# shield_confortimetro_bia.net
KiCad netlist of a schematic drawn in EAGLE
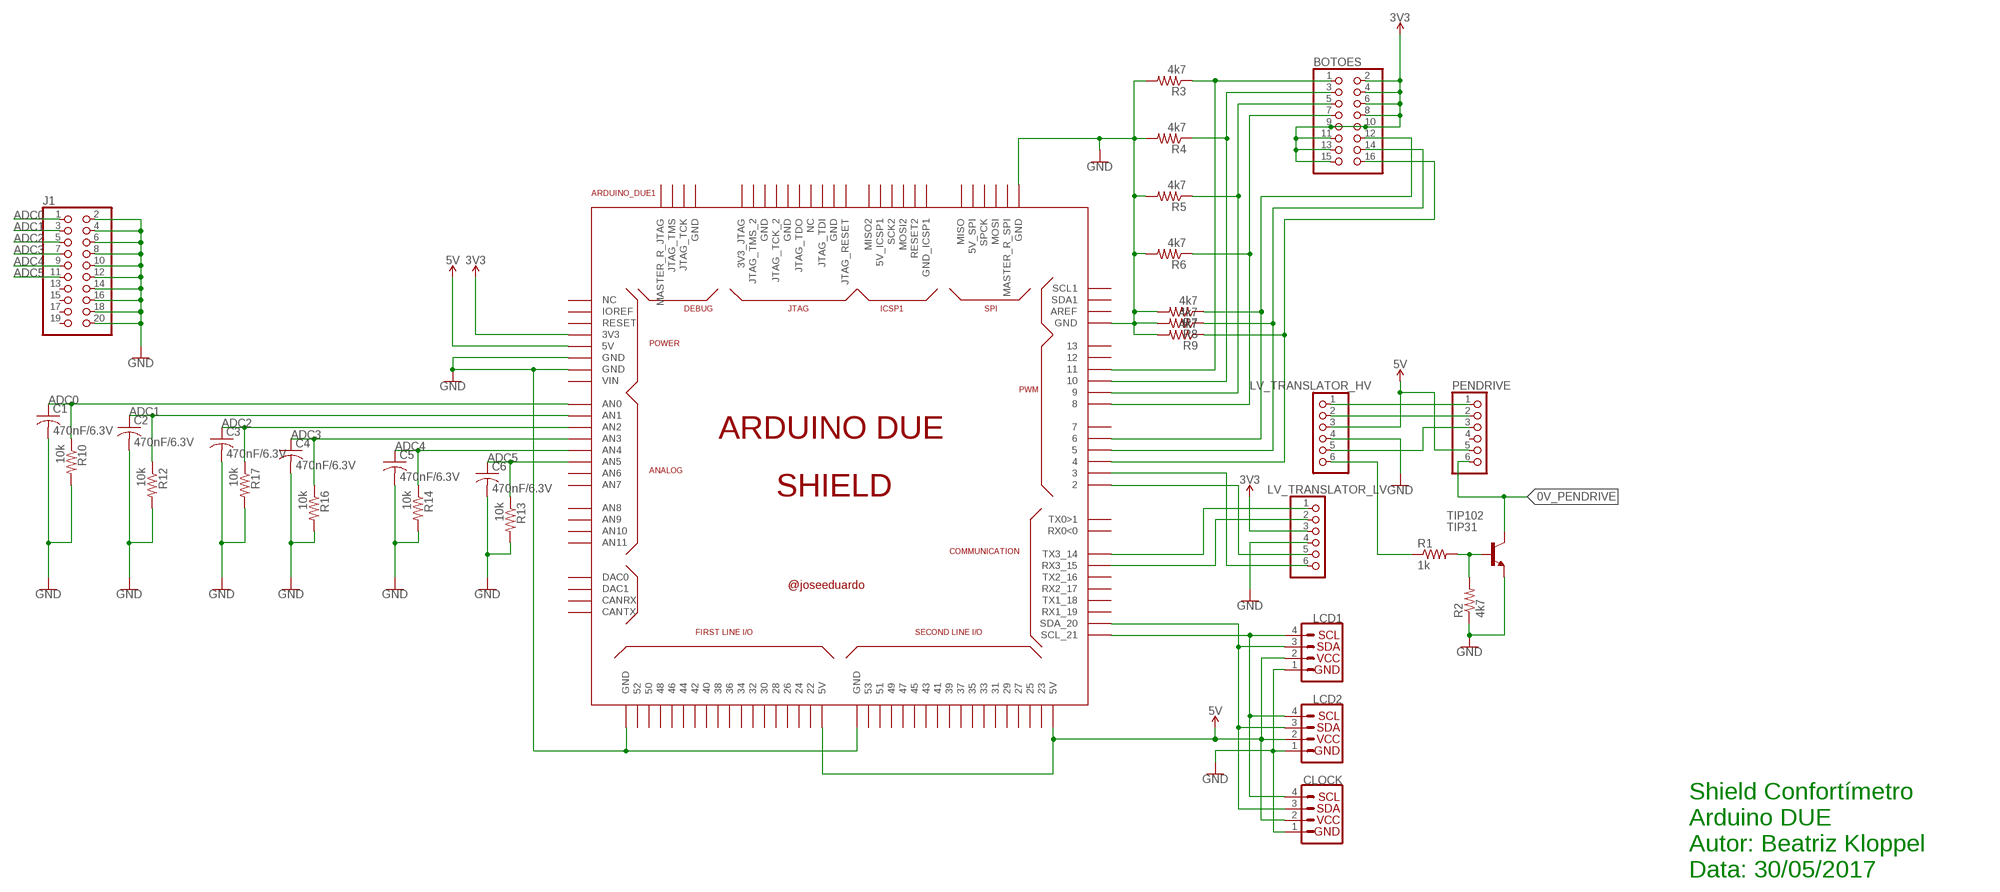
[diagram p0: schematic, sheet 1]

(export (version "E")
  (design (tool "Eeschema 10.0.6"))
  (components
    (comp (ref "ARDUINO_DUE1")
      (value "ARDUINO_DUE_SHIELD")
      (footprint "eagle-import:ARDUINO_DUE_SHIELD")
      (libsource (lib "eagle-import") (part "ARDUINO_DUE_SHIELD"))
    )
    (comp (ref "BOTOES")
      (value "PINHD-2X8")
      (footprint "eagle-import:2X08")
      (libsource (lib "eagle-import") (part "PINHD-2X8"))
    )
    (comp (ref "C1")
      (value "470nF/6.3V")
      (footprint "eagle-import:C050-030X075")
      (libsource (lib "eagle-import") (part "C-US050-030X075"))
    )
    (comp (ref "C2")
      (value "470nF/6.3V")
      (footprint "eagle-import:C050-030X075")
      (libsource (lib "eagle-import") (part "C-US050-030X075"))
    )
    (comp (ref "C3")
      (value "470nF/6.3V")
      (footprint "eagle-import:C050-030X075")
      (libsource (lib "eagle-import") (part "C-US050-030X075"))
    )
    (comp (ref "C4")
      (value "470nF/6.3V")
      (footprint "eagle-import:C050-030X075")
      (libsource (lib "eagle-import") (part "C-US050-030X075"))
    )
    (comp (ref "C5")
      (value "470nF/6.3V")
      (footprint "eagle-import:C050-030X075")
      (libsource (lib "eagle-import") (part "C-US050-030X075"))
    )
    (comp (ref "C6")
      (value "470nF/6.3V")
      (footprint "eagle-import:C050-030X075")
      (libsource (lib "eagle-import") (part "C-US050-030X075"))
    )
    (comp (ref "CLOCK")
      (value "I2C_STANDARD")
      (footprint "eagle-import:1X04")
      (libsource (lib "eagle-import") (part "I2C_STANDARD"))
    )
    (comp (ref "J1")
      (value "PINHD-2X10")
      (footprint "eagle-import:2X10")
      (libsource (lib "eagle-import") (part "PINHD-2X10"))
    )
    (comp (ref "LCD1")
      (value "I2C_STANDARD")
      (footprint "eagle-import:1X04")
      (libsource (lib "eagle-import") (part "I2C_STANDARD"))
    )
    (comp (ref "LCD2")
      (value "I2C_STANDARD")
      (footprint "eagle-import:1X04")
      (libsource (lib "eagle-import") (part "I2C_STANDARD"))
    )
    (comp (ref "LV_TRANSLATOR_HV")
      (value "PINHD-1X6")
      (footprint "eagle-import:1X06")
      (libsource (lib "eagle-import") (part "PINHD-1X6"))
    )
    (comp (ref "LV_TRANSLATOR_LV")
      (value "PINHD-1X6")
      (footprint "eagle-import:1X06")
      (libsource (lib "eagle-import") (part "PINHD-1X6"))
    )
    (comp (ref "PENDRIVE")
      (value "PINHD-1X6")
      (footprint "eagle-import:1X06")
      (libsource (lib "eagle-import") (part "PINHD-1X6"))
    )
    (comp (ref "R1")
      (value "1k")
      (footprint "eagle-import:0309_12")
      (libsource (lib "eagle-import") (part "R-US_0309/12"))
    )
    (comp (ref "R2")
      (value "4k7")
      (footprint "eagle-import:0309_12")
      (libsource (lib "eagle-import") (part "R-US_0309/12"))
    )
    (comp (ref "R3")
      (value "4k7")
      (footprint "eagle-import:0309_12")
      (libsource (lib "eagle-import") (part "R-US_0309/12"))
    )
    (comp (ref "R4")
      (value "4k7")
      (footprint "eagle-import:0309_12")
      (libsource (lib "eagle-import") (part "R-US_0309/12"))
    )
    (comp (ref "R5")
      (value "4k7")
      (footprint "eagle-import:0309_12")
      (libsource (lib "eagle-import") (part "R-US_0309/12"))
    )
    (comp (ref "R6")
      (value "4k7")
      (footprint "eagle-import:0309_12")
      (libsource (lib "eagle-import") (part "R-US_0309/12"))
    )
    (comp (ref "R7")
      (value "4k7")
      (footprint "eagle-import:0309_12")
      (libsource (lib "eagle-import") (part "R-US_0309/12"))
    )
    (comp (ref "R8")
      (value "4k7")
      (footprint "eagle-import:0309_12")
      (libsource (lib "eagle-import") (part "R-US_0309/12"))
    )
    (comp (ref "R9")
      (value "4k7")
      (footprint "eagle-import:0309_12")
      (libsource (lib "eagle-import") (part "R-US_0309/12"))
    )
    (comp (ref "R10")
      (value "10k")
      (footprint "eagle-import:0309_12")
      (libsource (lib "eagle-import") (part "R-US_0309/12"))
    )
    (comp (ref "R12")
      (value "10k")
      (footprint "eagle-import:0309_12")
      (libsource (lib "eagle-import") (part "R-US_0309/12"))
    )
    (comp (ref "R13")
      (value "10k")
      (footprint "eagle-import:0309_12")
      (libsource (lib "eagle-import") (part "R-US_0309/12"))
    )
    (comp (ref "R14")
      (value "10k")
      (footprint "eagle-import:0309_12")
      (libsource (lib "eagle-import") (part "R-US_0309/12"))
    )
    (comp (ref "R16")
      (value "10k")
      (footprint "eagle-import:0309_12")
      (libsource (lib "eagle-import") (part "R-US_0309/12"))
    )
    (comp (ref "R17")
      (value "10k")
      (footprint "eagle-import:0309_12")
      (libsource (lib "eagle-import") (part "R-US_0309/12"))
    )
    (comp (ref "TIP102")
      (value "TIP31")
      (footprint "eagle-import:TO220")
      (libsource (lib "eagle-import") (part "TIP31"))
    )
  )
  (nets
    (net (code "1") (name "/ADC0") (class "Default")
      (node (ref "ARDUINO_DUE1") (pin "A0") (pinfunction "AN0_A0") (pintype "bidirectional"))
      (node (ref "C1") (pin "1") (pinfunction "1_1") (pintype "passive"))
      (node (ref "J1") (pin "1") (pinfunction "1_1") (pintype "passive"))
      (node (ref "R10") (pin "1") (pinfunction "1_1") (pintype "passive"))
    )
    (net (code "2") (name "/ADC1") (class "Default")
      (node (ref "ARDUINO_DUE1") (pin "A1") (pinfunction "AN1_A1") (pintype "bidirectional"))
      (node (ref "C2") (pin "1") (pinfunction "1_1") (pintype "passive"))
      (node (ref "J1") (pin "3") (pinfunction "3_3") (pintype "passive"))
      (node (ref "R12") (pin "1") (pinfunction "1_1") (pintype "passive"))
    )
    (net (code "3") (name "/ADC2") (class "Default")
      (node (ref "ARDUINO_DUE1") (pin "A2") (pinfunction "AN2_A2") (pintype "bidirectional"))
      (node (ref "C3") (pin "1") (pinfunction "1_1") (pintype "passive"))
      (node (ref "J1") (pin "5") (pinfunction "5_5") (pintype "passive"))
      (node (ref "R17") (pin "1") (pinfunction "1_1") (pintype "passive"))
    )
    (net (code "4") (name "/ADC3") (class "Default")
      (node (ref "ARDUINO_DUE1") (pin "A3") (pinfunction "AN3_A3") (pintype "bidirectional"))
      (node (ref "C4") (pin "1") (pinfunction "1_1") (pintype "passive"))
      (node (ref "J1") (pin "7") (pinfunction "7_7") (pintype "passive"))
      (node (ref "R16") (pin "1") (pinfunction "1_1") (pintype "passive"))
    )
    (net (code "5") (name "/ADC4") (class "Default")
      (node (ref "ARDUINO_DUE1") (pin "A4") (pinfunction "AN4_A4") (pintype "bidirectional"))
      (node (ref "C5") (pin "1") (pinfunction "1_1") (pintype "passive"))
      (node (ref "J1") (pin "9") (pinfunction "9_9") (pintype "passive"))
      (node (ref "R14") (pin "1") (pinfunction "1_1") (pintype "passive"))
    )
    (net (code "6") (name "/ADC5") (class "Default")
      (node (ref "ARDUINO_DUE1") (pin "A5") (pinfunction "AN5_A5") (pintype "bidirectional"))
      (node (ref "C6") (pin "1") (pinfunction "1_1") (pintype "passive"))
      (node (ref "J1") (pin "11") (pinfunction "11_11") (pintype "passive"))
      (node (ref "R13") (pin "1") (pinfunction "1_1") (pintype "passive"))
    )
    (net (code "7") (name "0V_PENDRIVE") (class "Default")
      (node (ref "PENDRIVE") (pin "6") (pinfunction "6_6") (pintype "passive"))
      (node (ref "TIP102") (pin "2") (pinfunction "C_2") (pintype "passive"))
    )
    (net (code "8") (name "3V3") (class "Default")
      (node (ref "ARDUINO_DUE1") (pin "3V3") (pinfunction "3V3_3V3") (pintype "bidirectional"))
      (node (ref "BOTOES") (pin "10") (pinfunction "10_10") (pintype "passive"))
      (node (ref "BOTOES") (pin "11") (pinfunction "11_11") (pintype "passive"))
      (node (ref "BOTOES") (pin "13") (pinfunction "13_13") (pintype "passive"))
      (node (ref "BOTOES") (pin "15") (pinfunction "15_15") (pintype "passive"))
      (node (ref "BOTOES") (pin "2") (pinfunction "2_2") (pintype "passive"))
      (node (ref "BOTOES") (pin "4") (pinfunction "4_4") (pintype "passive"))
      (node (ref "BOTOES") (pin "6") (pinfunction "6_6") (pintype "passive"))
      (node (ref "BOTOES") (pin "8") (pinfunction "8_8") (pintype "passive"))
      (node (ref "BOTOES") (pin "9") (pinfunction "9_9") (pintype "passive"))
      (node (ref "LV_TRANSLATOR_LV") (pin "3") (pinfunction "3_3") (pintype "passive"))
    )
    (net (code "9") (name "5V") (class "Default")
      (node (ref "ARDUINO_DUE1") (pin "5V0") (pinfunction "5V_5V0") (pintype "bidirectional"))
      (node (ref "ARDUINO_DUE1") (pin "5V0_1") (pinfunction "5V_5V0_1") (pintype "bidirectional"))
      (node (ref "ARDUINO_DUE1") (pin "5V0_2") (pinfunction "5V_5V0_2") (pintype "bidirectional"))
      (node (ref "CLOCK") (pin "2") (pinfunction "2_2") (pintype "power_in"))
      (node (ref "LCD1") (pin "2") (pinfunction "2_2") (pintype "power_in"))
      (node (ref "LCD2") (pin "2") (pinfunction "2_2") (pintype "power_in"))
      (node (ref "LV_TRANSLATOR_HV") (pin "3") (pinfunction "3_3") (pintype "passive"))
      (node (ref "PENDRIVE") (pin "5") (pinfunction "5_5") (pintype "passive"))
    )
    (net (code "10") (name "GND") (class "Default")
      (node (ref "ARDUINO_DUE1") (pin "GND") (pinfunction "GND_GND") (pintype "bidirectional"))
      (node (ref "ARDUINO_DUE1") (pin "GND_1") (pinfunction "GND_GND_1") (pintype "bidirectional"))
      (node (ref "ARDUINO_DUE1") (pin "GND_2") (pinfunction "GND_GND_2") (pintype "bidirectional"))
      (node (ref "ARDUINO_DUE1") (pin "GND_3") (pinfunction "GND_GND_3") (pintype "bidirectional"))
      (node (ref "ARDUINO_DUE1") (pin "GND_4") (pinfunction "GND_GND_4") (pintype "bidirectional"))
      (node (ref "ARDUINO_DUE1") (pin "GND_5") (pinfunction "GND_GND_5") (pintype "bidirectional"))
      (node (ref "C1") (pin "2") (pinfunction "2_2") (pintype "passive"))
      (node (ref "C2") (pin "2") (pinfunction "2_2") (pintype "passive"))
      (node (ref "C3") (pin "2") (pinfunction "2_2") (pintype "passive"))
      (node (ref "C4") (pin "2") (pinfunction "2_2") (pintype "passive"))
      (node (ref "C5") (pin "2") (pinfunction "2_2") (pintype "passive"))
      (node (ref "C6") (pin "2") (pinfunction "2_2") (pintype "passive"))
      (node (ref "CLOCK") (pin "1") (pinfunction "1_1") (pintype "power_in"))
      (node (ref "J1") (pin "10") (pinfunction "10_10") (pintype "passive"))
      (node (ref "J1") (pin "12") (pinfunction "12_12") (pintype "passive"))
      (node (ref "J1") (pin "14") (pinfunction "14_14") (pintype "passive"))
      (node (ref "J1") (pin "16") (pinfunction "16_16") (pintype "passive"))
      (node (ref "J1") (pin "18") (pinfunction "18_18") (pintype "passive"))
      (node (ref "J1") (pin "2") (pinfunction "2_2") (pintype "passive"))
      (node (ref "J1") (pin "20") (pinfunction "20_20") (pintype "passive"))
      (node (ref "J1") (pin "4") (pinfunction "4_4") (pintype "passive"))
      (node (ref "J1") (pin "6") (pinfunction "6_6") (pintype "passive"))
      (node (ref "J1") (pin "8") (pinfunction "8_8") (pintype "passive"))
      (node (ref "LCD1") (pin "1") (pinfunction "1_1") (pintype "power_in"))
      (node (ref "LCD2") (pin "1") (pinfunction "1_1") (pintype "power_in"))
      (node (ref "LV_TRANSLATOR_HV") (pin "4") (pinfunction "4_4") (pintype "passive"))
      (node (ref "LV_TRANSLATOR_LV") (pin "4") (pinfunction "4_4") (pintype "passive"))
      (node (ref "R10") (pin "2") (pinfunction "2_2") (pintype "passive"))
      (node (ref "R12") (pin "2") (pinfunction "2_2") (pintype "passive"))
      (node (ref "R13") (pin "2") (pinfunction "2_2") (pintype "passive"))
      (node (ref "R14") (pin "2") (pinfunction "2_2") (pintype "passive"))
      (node (ref "R16") (pin "2") (pinfunction "2_2") (pintype "passive"))
      (node (ref "R17") (pin "2") (pinfunction "2_2") (pintype "passive"))
      (node (ref "R2") (pin "1") (pinfunction "1_1") (pintype "passive"))
      (node (ref "R3") (pin "2") (pinfunction "2_2") (pintype "passive"))
      (node (ref "R4") (pin "2") (pinfunction "2_2") (pintype "passive"))
      (node (ref "R5") (pin "2") (pinfunction "2_2") (pintype "passive"))
      (node (ref "R6") (pin "2") (pinfunction "2_2") (pintype "passive"))
      (node (ref "R7") (pin "2") (pinfunction "2_2") (pintype "passive"))
      (node (ref "R8") (pin "2") (pinfunction "2_2") (pintype "passive"))
      (node (ref "R9") (pin "2") (pinfunction "2_2") (pintype "passive"))
      (node (ref "TIP102") (pin "3") (pinfunction "E_3") (pintype "passive"))
    )
    (net (code "11") (name "Net-(ARDUINO_DUE1-Pad2)") (class "Default")
      (node (ref "ARDUINO_DUE1") (pin "2") (pinfunction "2_2") (pintype "bidirectional"))
      (node (ref "LV_TRANSLATOR_LV") (pin "5") (pinfunction "5_5") (pintype "passive"))
    )
    (net (code "12") (name "Net-(ARDUINO_DUE1-Pad3)") (class "Default")
      (node (ref "ARDUINO_DUE1") (pin "3") (pinfunction "3_3") (pintype "bidirectional"))
      (node (ref "LV_TRANSLATOR_LV") (pin "6") (pinfunction "6_6") (pintype "passive"))
    )
    (net (code "13") (name "Net-(ARDUINO_DUE1-Pad4)") (class "Default")
      (node (ref "ARDUINO_DUE1") (pin "4") (pinfunction "4_4") (pintype "bidirectional"))
      (node (ref "BOTOES") (pin "16") (pinfunction "16_16") (pintype "passive"))
      (node (ref "R9") (pin "1") (pinfunction "1_1") (pintype "passive"))
    )
    (net (code "14") (name "Net-(ARDUINO_DUE1-Pad5)") (class "Default")
      (node (ref "ARDUINO_DUE1") (pin "5") (pinfunction "5_5") (pintype "bidirectional"))
      (node (ref "BOTOES") (pin "14") (pinfunction "14_14") (pintype "passive"))
      (node (ref "R8") (pin "1") (pinfunction "1_1") (pintype "passive"))
    )
    (net (code "15") (name "Net-(ARDUINO_DUE1-Pad6)") (class "Default")
      (node (ref "ARDUINO_DUE1") (pin "6") (pinfunction "6_6") (pintype "bidirectional"))
      (node (ref "BOTOES") (pin "12") (pinfunction "12_12") (pintype "passive"))
      (node (ref "R7") (pin "1") (pinfunction "1_1") (pintype "passive"))
    )
    (net (code "16") (name "Net-(ARDUINO_DUE1-Pad8)") (class "Default")
      (node (ref "ARDUINO_DUE1") (pin "8") (pinfunction "8_8") (pintype "bidirectional"))
      (node (ref "BOTOES") (pin "7") (pinfunction "7_7") (pintype "passive"))
      (node (ref "R6") (pin "1") (pinfunction "1_1") (pintype "passive"))
    )
    (net (code "17") (name "Net-(ARDUINO_DUE1-Pad9)") (class "Default")
      (node (ref "ARDUINO_DUE1") (pin "9") (pinfunction "9_9") (pintype "bidirectional"))
      (node (ref "BOTOES") (pin "5") (pinfunction "5_5") (pintype "passive"))
      (node (ref "R5") (pin "1") (pinfunction "1_1") (pintype "passive"))
    )
    (net (code "18") (name "Net-(ARDUINO_DUE1-Pad10)") (class "Default")
      (node (ref "ARDUINO_DUE1") (pin "10") (pinfunction "10_10") (pintype "bidirectional"))
      (node (ref "BOTOES") (pin "3") (pinfunction "3_3") (pintype "passive"))
      (node (ref "R4") (pin "1") (pinfunction "1_1") (pintype "passive"))
    )
    (net (code "19") (name "Net-(ARDUINO_DUE1-Pad11)") (class "Default")
      (node (ref "ARDUINO_DUE1") (pin "11") (pinfunction "11_11") (pintype "bidirectional"))
      (node (ref "BOTOES") (pin "1") (pinfunction "1_1") (pintype "passive"))
      (node (ref "R3") (pin "1") (pinfunction "1_1") (pintype "passive"))
    )
    (net (code "20") (name "Net-(ARDUINO_DUE1-RX3_15)") (class "Default")
      (node (ref "ARDUINO_DUE1") (pin "15") (pinfunction "RX3_15_15") (pintype "bidirectional"))
      (node (ref "LV_TRANSLATOR_LV") (pin "2") (pinfunction "2_2") (pintype "passive"))
    )
    (net (code "21") (name "Net-(ARDUINO_DUE1-SCL_21)") (class "Default")
      (node (ref "ARDUINO_DUE1") (pin "21") (pinfunction "SCL_21_21") (pintype "bidirectional"))
      (node (ref "CLOCK") (pin "4") (pinfunction "4_4") (pintype "passive"))
      (node (ref "LCD1") (pin "4") (pinfunction "4_4") (pintype "passive"))
      (node (ref "LCD2") (pin "4") (pinfunction "4_4") (pintype "passive"))
    )
    (net (code "22") (name "Net-(ARDUINO_DUE1-SDA_20)") (class "Default")
      (node (ref "ARDUINO_DUE1") (pin "20") (pinfunction "SDA_20_20") (pintype "bidirectional"))
      (node (ref "CLOCK") (pin "3") (pinfunction "3_3") (pintype "passive"))
      (node (ref "LCD1") (pin "3") (pinfunction "3_3") (pintype "passive"))
      (node (ref "LCD2") (pin "3") (pinfunction "3_3") (pintype "passive"))
    )
    (net (code "23") (name "Net-(ARDUINO_DUE1-TX3_14)") (class "Default")
      (node (ref "ARDUINO_DUE1") (pin "14") (pinfunction "TX3_14_14") (pintype "bidirectional"))
      (node (ref "LV_TRANSLATOR_LV") (pin "1") (pinfunction "1_1") (pintype "passive"))
    )
    (net (code "24") (name "Net-(LV_TRANSLATOR_HV-Pad1)") (class "Default")
      (node (ref "LV_TRANSLATOR_HV") (pin "1") (pinfunction "1_1") (pintype "passive"))
      (node (ref "PENDRIVE") (pin "1") (pinfunction "1_1") (pintype "passive"))
    )
    (net (code "25") (name "Net-(LV_TRANSLATOR_HV-Pad2)") (class "Default")
      (node (ref "LV_TRANSLATOR_HV") (pin "2") (pinfunction "2_2") (pintype "passive"))
      (node (ref "PENDRIVE") (pin "2") (pinfunction "2_2") (pintype "passive"))
    )
    (net (code "26") (name "Net-(LV_TRANSLATOR_HV-Pad5)") (class "Default")
      (node (ref "LV_TRANSLATOR_HV") (pin "5") (pinfunction "5_5") (pintype "passive"))
      (node (ref "PENDRIVE") (pin "3") (pinfunction "3_3") (pintype "passive"))
    )
    (net (code "27") (name "Net-(LV_TRANSLATOR_HV-Pad6)") (class "Default")
      (node (ref "LV_TRANSLATOR_HV") (pin "6") (pinfunction "6_6") (pintype "passive"))
      (node (ref "R1") (pin "1") (pinfunction "1_1") (pintype "passive"))
    )
    (net (code "28") (name "Net-(TIP102-B)") (class "Default")
      (node (ref "R1") (pin "2") (pinfunction "2_2") (pintype "passive"))
      (node (ref "R2") (pin "2") (pinfunction "2_2") (pintype "passive"))
      (node (ref "TIP102") (pin "1") (pinfunction "B_1") (pintype "passive"))
    )
    (net (code "29") (name "unconnected-(ARDUINO_DUE1-5V_SPI-Pad5V_2)") (class "Default")
      (node (ref "ARDUINO_DUE1") (pin "5V_2") (pinfunction "5V_SPI_5V_2") (pintype "bidirectional"))
    )
    (net (code "30") (name "unconnected-(ARDUINO_DUE1-AN6-PadA6)") (class "Default")
      (node (ref "ARDUINO_DUE1") (pin "A6") (pinfunction "AN6_A6") (pintype "bidirectional"))
    )
    (net (code "31") (name "unconnected-(ARDUINO_DUE1-AN7-PadA7)") (class "Default")
      (node (ref "ARDUINO_DUE1") (pin "A7") (pinfunction "AN7_A7") (pintype "bidirectional"))
    )
    (net (code "32") (name "unconnected-(ARDUINO_DUE1-AN8-PadA8)") (class "Default")
      (node (ref "ARDUINO_DUE1") (pin "A8") (pinfunction "AN8_A8") (pintype "bidirectional"))
    )
    (net (code "33") (name "unconnected-(ARDUINO_DUE1-AN9-PadA9)") (class "Default")
      (node (ref "ARDUINO_DUE1") (pin "A9") (pinfunction "AN9_A9") (pintype "bidirectional"))
    )
    (net (code "34") (name "unconnected-(ARDUINO_DUE1-AN10-PadA10)") (class "Default")
      (node (ref "ARDUINO_DUE1") (pin "A10") (pinfunction "AN10_A10") (pintype "bidirectional"))
    )
    (net (code "35") (name "unconnected-(ARDUINO_DUE1-AN11-PadA11)") (class "Default")
      (node (ref "ARDUINO_DUE1") (pin "A11") (pinfunction "AN11_A11") (pintype "bidirectional"))
    )
    (net (code "36") (name "unconnected-(ARDUINO_DUE1-GND-PadGND_7)") (class "Default")
      (node (ref "ARDUINO_DUE1") (pin "GND_7") (pinfunction "GND_GND_7") (pintype "bidirectional"))
    )
    (net (code "37") (name "unconnected-(ARDUINO_DUE1-GND-PadGND_8)") (class "Default")
      (node (ref "ARDUINO_DUE1") (pin "GND_8") (pinfunction "GND_GND_8") (pintype "bidirectional"))
    )
    (net (code "38") (name "unconnected-(ARDUINO_DUE1-GND-PadGND_9)") (class "Default")
      (node (ref "ARDUINO_DUE1") (pin "GND_9") (pinfunction "GND_GND_9") (pintype "bidirectional"))
    )
    (net (code "39") (name "unconnected-(ARDUINO_DUE1-GND-PadGND_10)") (class "Default")
      (node (ref "ARDUINO_DUE1") (pin "GND_10") (pinfunction "GND_GND_10") (pintype "bidirectional"))
    )
    (net (code "40") (name "unconnected-(ARDUINO_DUE1-MASTER_R_JTAG-PadMASTER_RESET_JTAG)") (class "Default")
      (node (ref "ARDUINO_DUE1") (pin "MASTER_RESET_JTAG") (pinfunction "MASTER_R_JTAG_MASTER_RESET_JTAG") (pintype "bidirectional"))
    )
    (net (code "41") (name "unconnected-(ARDUINO_DUE1-MASTER_R_SPI-PadMASTER_RESET_SPI)") (class "Default")
      (node (ref "ARDUINO_DUE1") (pin "MASTER_RESET_SPI") (pinfunction "MASTER_R_SPI_MASTER_RESET_SPI") (pintype "bidirectional"))
    )
    (net (code "42") (name "unconnected-(ARDUINO_DUE1-NC-PadNC_2)") (class "Default")
      (node (ref "ARDUINO_DUE1") (pin "NC_2") (pinfunction "NC_NC_2") (pintype "no_connect"))
    )
    (net (code "43") (name "unconnected-(ARDUINO_DUE1-NC-PadNC_5)") (class "Default")
      (node (ref "ARDUINO_DUE1") (pin "NC_5") (pinfunction "NC_NC_5") (pintype "bidirectional"))
    )
    (net (code "44") (name "unconnected-(ARDUINO_DUE1-Pad3V3_JTAG)") (class "Default")
      (node (ref "ARDUINO_DUE1") (pin "3V3_JTAG") (pinfunction "3V3_JTAG_3V3_JTAG") (pintype "bidirectional"))
    )
    (net (code "45") (name "unconnected-(ARDUINO_DUE1-Pad5V_ICSP1)") (class "Default")
      (node (ref "ARDUINO_DUE1") (pin "5V_ICSP1") (pinfunction "5V_ICSP1_5V_ICSP1") (pintype "bidirectional"))
    )
    (net (code "46") (name "unconnected-(ARDUINO_DUE1-Pad7)") (class "Default")
      (node (ref "ARDUINO_DUE1") (pin "7") (pinfunction "7_7") (pintype "bidirectional"))
    )
    (net (code "47") (name "unconnected-(ARDUINO_DUE1-Pad12)") (class "Default")
      (node (ref "ARDUINO_DUE1") (pin "12") (pinfunction "12_12") (pintype "bidirectional"))
    )
    (net (code "48") (name "unconnected-(ARDUINO_DUE1-Pad13)") (class "Default")
      (node (ref "ARDUINO_DUE1") (pin "13") (pinfunction "13_13") (pintype "bidirectional"))
    )
    (net (code "49") (name "unconnected-(ARDUINO_DUE1-Pad22)") (class "Default")
      (node (ref "ARDUINO_DUE1") (pin "22") (pinfunction "22_22") (pintype "bidirectional"))
    )
    (net (code "50") (name "unconnected-(ARDUINO_DUE1-Pad23)") (class "Default")
      (node (ref "ARDUINO_DUE1") (pin "23") (pinfunction "23_23") (pintype "bidirectional"))
    )
    (net (code "51") (name "unconnected-(ARDUINO_DUE1-Pad24)") (class "Default")
      (node (ref "ARDUINO_DUE1") (pin "24") (pinfunction "24_24") (pintype "bidirectional"))
    )
    (net (code "52") (name "unconnected-(ARDUINO_DUE1-Pad25)") (class "Default")
      (node (ref "ARDUINO_DUE1") (pin "25") (pinfunction "25_25") (pintype "bidirectional"))
    )
    (net (code "53") (name "unconnected-(ARDUINO_DUE1-Pad26)") (class "Default")
      (node (ref "ARDUINO_DUE1") (pin "26") (pinfunction "26_26") (pintype "bidirectional"))
    )
    (net (code "54") (name "unconnected-(ARDUINO_DUE1-Pad27)") (class "Default")
      (node (ref "ARDUINO_DUE1") (pin "27") (pinfunction "27_27") (pintype "bidirectional"))
    )
    (net (code "55") (name "unconnected-(ARDUINO_DUE1-Pad28)") (class "Default")
      (node (ref "ARDUINO_DUE1") (pin "28") (pinfunction "28_28") (pintype "bidirectional"))
    )
    (net (code "56") (name "unconnected-(ARDUINO_DUE1-Pad29)") (class "Default")
      (node (ref "ARDUINO_DUE1") (pin "29") (pinfunction "29_29") (pintype "bidirectional"))
    )
    (net (code "57") (name "unconnected-(ARDUINO_DUE1-Pad30)") (class "Default")
      (node (ref "ARDUINO_DUE1") (pin "30") (pinfunction "30_30") (pintype "bidirectional"))
    )
    (net (code "58") (name "unconnected-(ARDUINO_DUE1-Pad31)") (class "Default")
      (node (ref "ARDUINO_DUE1") (pin "31") (pinfunction "31_31") (pintype "bidirectional"))
    )
    (net (code "59") (name "unconnected-(ARDUINO_DUE1-Pad32)") (class "Default")
      (node (ref "ARDUINO_DUE1") (pin "32") (pinfunction "32_32") (pintype "bidirectional"))
    )
    (net (code "60") (name "unconnected-(ARDUINO_DUE1-Pad33)") (class "Default")
      (node (ref "ARDUINO_DUE1") (pin "33") (pinfunction "33_33") (pintype "bidirectional"))
    )
    (net (code "61") (name "unconnected-(ARDUINO_DUE1-Pad34)") (class "Default")
      (node (ref "ARDUINO_DUE1") (pin "34") (pinfunction "34_34") (pintype "bidirectional"))
    )
    (net (code "62") (name "unconnected-(ARDUINO_DUE1-Pad35)") (class "Default")
      (node (ref "ARDUINO_DUE1") (pin "35") (pinfunction "35_35") (pintype "bidirectional"))
    )
    (net (code "63") (name "unconnected-(ARDUINO_DUE1-Pad36)") (class "Default")
      (node (ref "ARDUINO_DUE1") (pin "36") (pinfunction "36_36") (pintype "bidirectional"))
    )
    (net (code "64") (name "unconnected-(ARDUINO_DUE1-Pad37)") (class "Default")
      (node (ref "ARDUINO_DUE1") (pin "37") (pinfunction "37_37") (pintype "bidirectional"))
    )
    (net (code "65") (name "unconnected-(ARDUINO_DUE1-Pad38)") (class "Default")
      (node (ref "ARDUINO_DUE1") (pin "38") (pinfunction "38_38") (pintype "bidirectional"))
    )
    (net (code "66") (name "unconnected-(ARDUINO_DUE1-Pad39)") (class "Default")
      (node (ref "ARDUINO_DUE1") (pin "39") (pinfunction "39_39") (pintype "bidirectional"))
    )
    (net (code "67") (name "unconnected-(ARDUINO_DUE1-Pad40)") (class "Default")
      (node (ref "ARDUINO_DUE1") (pin "40") (pinfunction "40_40") (pintype "bidirectional"))
    )
    (net (code "68") (name "unconnected-(ARDUINO_DUE1-Pad41)") (class "Default")
      (node (ref "ARDUINO_DUE1") (pin "41") (pinfunction "41_41") (pintype "bidirectional"))
    )
    (net (code "69") (name "unconnected-(ARDUINO_DUE1-Pad42)") (class "Default")
      (node (ref "ARDUINO_DUE1") (pin "42") (pinfunction "42_42") (pintype "bidirectional"))
    )
    (net (code "70") (name "unconnected-(ARDUINO_DUE1-Pad43)") (class "Default")
      (node (ref "ARDUINO_DUE1") (pin "43") (pinfunction "43_43") (pintype "bidirectional"))
    )
    (net (code "71") (name "unconnected-(ARDUINO_DUE1-Pad44)") (class "Default")
      (node (ref "ARDUINO_DUE1") (pin "44") (pinfunction "44_44") (pintype "bidirectional"))
    )
    (net (code "72") (name "unconnected-(ARDUINO_DUE1-Pad45)") (class "Default")
      (node (ref "ARDUINO_DUE1") (pin "45") (pinfunction "45_45") (pintype "bidirectional"))
    )
    (net (code "73") (name "unconnected-(ARDUINO_DUE1-Pad46)") (class "Default")
      (node (ref "ARDUINO_DUE1") (pin "46") (pinfunction "46_46") (pintype "bidirectional"))
    )
    (net (code "74") (name "unconnected-(ARDUINO_DUE1-Pad47)") (class "Default")
      (node (ref "ARDUINO_DUE1") (pin "47") (pinfunction "47_47") (pintype "bidirectional"))
    )
    (net (code "75") (name "unconnected-(ARDUINO_DUE1-Pad48)") (class "Default")
      (node (ref "ARDUINO_DUE1") (pin "48") (pinfunction "48_48") (pintype "bidirectional"))
    )
    (net (code "76") (name "unconnected-(ARDUINO_DUE1-Pad49)") (class "Default")
      (node (ref "ARDUINO_DUE1") (pin "49") (pinfunction "49_49") (pintype "bidirectional"))
    )
    (net (code "77") (name "unconnected-(ARDUINO_DUE1-Pad50)") (class "Default")
      (node (ref "ARDUINO_DUE1") (pin "50") (pinfunction "50_50") (pintype "bidirectional"))
    )
    (net (code "78") (name "unconnected-(ARDUINO_DUE1-Pad51)") (class "Default")
      (node (ref "ARDUINO_DUE1") (pin "51") (pinfunction "51_51") (pintype "bidirectional"))
    )
    (net (code "79") (name "unconnected-(ARDUINO_DUE1-Pad52)") (class "Default")
      (node (ref "ARDUINO_DUE1") (pin "52") (pinfunction "52_52") (pintype "bidirectional"))
    )
    (net (code "80") (name "unconnected-(ARDUINO_DUE1-Pad53)") (class "Default")
      (node (ref "ARDUINO_DUE1") (pin "53") (pinfunction "53_53") (pintype "bidirectional"))
    )
    (net (code "81") (name "unconnected-(ARDUINO_DUE1-PadAREF)") (class "Default")
      (node (ref "ARDUINO_DUE1") (pin "AREF") (pinfunction "AREF_AREF") (pintype "bidirectional"))
    )
    (net (code "82") (name "unconnected-(ARDUINO_DUE1-PadCANRX)") (class "Default")
      (node (ref "ARDUINO_DUE1") (pin "CANRX") (pinfunction "CANRX_CANRX") (pintype "bidirectional"))
    )
    (net (code "83") (name "unconnected-(ARDUINO_DUE1-PadCANTX)") (class "Default")
      (node (ref "ARDUINO_DUE1") (pin "CANTX") (pinfunction "CANTX_CANTX") (pintype "bidirectional"))
    )
    (net (code "84") (name "unconnected-(ARDUINO_DUE1-PadDAC0)") (class "Default")
      (node (ref "ARDUINO_DUE1") (pin "DAC0") (pinfunction "DAC0_DAC0") (pintype "bidirectional"))
    )
    (net (code "85") (name "unconnected-(ARDUINO_DUE1-PadDAC1)") (class "Default")
      (node (ref "ARDUINO_DUE1") (pin "DAC1") (pinfunction "DAC1_DAC1") (pintype "bidirectional"))
    )
    (net (code "86") (name "unconnected-(ARDUINO_DUE1-PadGND_ICSP1)") (class "Default")
      (node (ref "ARDUINO_DUE1") (pin "GND_ICSP1") (pinfunction "GND_ICSP1_GND_ICSP1") (pintype "bidirectional"))
    )
    (net (code "87") (name "unconnected-(ARDUINO_DUE1-PadIOREF)") (class "Default")
      (node (ref "ARDUINO_DUE1") (pin "IOREF") (pinfunction "IOREF_IOREF") (pintype "bidirectional"))
    )
    (net (code "88") (name "unconnected-(ARDUINO_DUE1-PadJTAG_RESET)") (class "Default")
      (node (ref "ARDUINO_DUE1") (pin "JTAG_RESET") (pinfunction "JTAG_RESET_JTAG_RESET") (pintype "bidirectional"))
    )
    (net (code "89") (name "unconnected-(ARDUINO_DUE1-PadJTAG_TCK)") (class "Default")
      (node (ref "ARDUINO_DUE1") (pin "JTAG_TCK") (pinfunction "JTAG_TCK_JTAG_TCK") (pintype "bidirectional"))
    )
    (net (code "90") (name "unconnected-(ARDUINO_DUE1-PadJTAG_TCK_2)") (class "Default")
      (node (ref "ARDUINO_DUE1") (pin "JTAG_TCK_2") (pinfunction "JTAG_TCK_2_JTAG_TCK_2") (pintype "bidirectional"))
    )
    (net (code "91") (name "unconnected-(ARDUINO_DUE1-PadJTAG_TDI)") (class "Default")
      (node (ref "ARDUINO_DUE1") (pin "JTAG_TDI") (pinfunction "JTAG_TDI_JTAG_TDI") (pintype "bidirectional"))
    )
    (net (code "92") (name "unconnected-(ARDUINO_DUE1-PadJTAG_TDO)") (class "Default")
      (node (ref "ARDUINO_DUE1") (pin "JTAG_TDO") (pinfunction "JTAG_TDO_JTAG_TDO") (pintype "bidirectional"))
    )
    (net (code "93") (name "unconnected-(ARDUINO_DUE1-PadJTAG_TMS)") (class "Default")
      (node (ref "ARDUINO_DUE1") (pin "JTAG_TMS") (pinfunction "JTAG_TMS_JTAG_TMS") (pintype "bidirectional"))
    )
    (net (code "94") (name "unconnected-(ARDUINO_DUE1-PadJTAG_TMS_2)") (class "Default")
      (node (ref "ARDUINO_DUE1") (pin "JTAG_TMS_2") (pinfunction "JTAG_TMS_2_JTAG_TMS_2") (pintype "bidirectional"))
    )
    (net (code "95") (name "unconnected-(ARDUINO_DUE1-PadMISO)") (class "Default")
      (node (ref "ARDUINO_DUE1") (pin "MISO") (pinfunction "MISO_MISO") (pintype "bidirectional"))
    )
    (net (code "96") (name "unconnected-(ARDUINO_DUE1-PadMISO2)") (class "Default")
      (node (ref "ARDUINO_DUE1") (pin "MISO2") (pinfunction "MISO2_MISO2") (pintype "bidirectional"))
    )
    (net (code "97") (name "unconnected-(ARDUINO_DUE1-PadMOSI)") (class "Default")
      (node (ref "ARDUINO_DUE1") (pin "MOSI") (pinfunction "MOSI_MOSI") (pintype "bidirectional"))
    )
    (net (code "98") (name "unconnected-(ARDUINO_DUE1-PadMOSI2)") (class "Default")
      (node (ref "ARDUINO_DUE1") (pin "MOSI2") (pinfunction "MOSI2_MOSI2") (pintype "bidirectional"))
    )
    (net (code "99") (name "unconnected-(ARDUINO_DUE1-PadRESET)") (class "Default")
      (node (ref "ARDUINO_DUE1") (pin "RESET") (pinfunction "RESET_RESET") (pintype "bidirectional"))
    )
    (net (code "100") (name "unconnected-(ARDUINO_DUE1-PadRESET2)") (class "Default")
      (node (ref "ARDUINO_DUE1") (pin "RESET2") (pinfunction "RESET2_RESET2") (pintype "bidirectional"))
    )
    (net (code "101") (name "unconnected-(ARDUINO_DUE1-PadSCK2)") (class "Default")
      (node (ref "ARDUINO_DUE1") (pin "SCK2") (pinfunction "SCK2_SCK2") (pintype "bidirectional"))
    )
    (net (code "102") (name "unconnected-(ARDUINO_DUE1-PadSCL1)") (class "Default")
      (node (ref "ARDUINO_DUE1") (pin "SCL1") (pinfunction "SCL1_SCL1") (pintype "bidirectional"))
    )
    (net (code "103") (name "unconnected-(ARDUINO_DUE1-PadSDA1)") (class "Default")
      (node (ref "ARDUINO_DUE1") (pin "SDA1") (pinfunction "SDA1_SDA1") (pintype "bidirectional"))
    )
    (net (code "104") (name "unconnected-(ARDUINO_DUE1-PadSPCK)") (class "Default")
      (node (ref "ARDUINO_DUE1") (pin "SPCK") (pinfunction "SPCK_SPCK") (pintype "bidirectional"))
    )
    (net (code "105") (name "unconnected-(ARDUINO_DUE1-PadVIN)") (class "Default")
      (node (ref "ARDUINO_DUE1") (pin "VIN") (pinfunction "VIN_VIN") (pintype "bidirectional"))
    )
    (net (code "106") (name "unconnected-(ARDUINO_DUE1-RX0<0-Pad0)") (class "Default")
      (node (ref "ARDUINO_DUE1") (pin "0") (pinfunction "RX0<0_0") (pintype "bidirectional"))
    )
    (net (code "107") (name "unconnected-(ARDUINO_DUE1-RX1_19-Pad19)") (class "Default")
      (node (ref "ARDUINO_DUE1") (pin "19") (pinfunction "RX1_19_19") (pintype "bidirectional"))
    )
    (net (code "108") (name "unconnected-(ARDUINO_DUE1-RX2_17-Pad17)") (class "Default")
      (node (ref "ARDUINO_DUE1") (pin "17") (pinfunction "RX2_17_17") (pintype "bidirectional"))
    )
    (net (code "109") (name "unconnected-(ARDUINO_DUE1-TX0>1-Pad1)") (class "Default")
      (node (ref "ARDUINO_DUE1") (pin "1") (pinfunction "TX0>1_1") (pintype "bidirectional"))
    )
    (net (code "110") (name "unconnected-(ARDUINO_DUE1-TX1_18-Pad18)") (class "Default")
      (node (ref "ARDUINO_DUE1") (pin "18") (pinfunction "TX1_18_18") (pintype "bidirectional"))
    )
    (net (code "111") (name "unconnected-(ARDUINO_DUE1-TX2_16-Pad16)") (class "Default")
      (node (ref "ARDUINO_DUE1") (pin "16") (pinfunction "TX2_16_16") (pintype "bidirectional"))
    )
    (net (code "112") (name "unconnected-(J1-Pad13)") (class "Default")
      (node (ref "J1") (pin "13") (pinfunction "13_13") (pintype "passive"))
    )
    (net (code "113") (name "unconnected-(J1-Pad15)") (class "Default")
      (node (ref "J1") (pin "15") (pinfunction "15_15") (pintype "passive"))
    )
    (net (code "114") (name "unconnected-(J1-Pad17)") (class "Default")
      (node (ref "J1") (pin "17") (pinfunction "17_17") (pintype "passive"))
    )
    (net (code "115") (name "unconnected-(J1-Pad19)") (class "Default")
      (node (ref "J1") (pin "19") (pinfunction "19_19") (pintype "passive"))
    )
    (net (code "116") (name "unconnected-(PENDRIVE-Pad4)") (class "Default")
      (node (ref "PENDRIVE") (pin "4") (pinfunction "4_4") (pintype "passive"))
    )
  )
)
